# cpu_board.net
KiCad netlist of a schematic drawn in Altium Designer
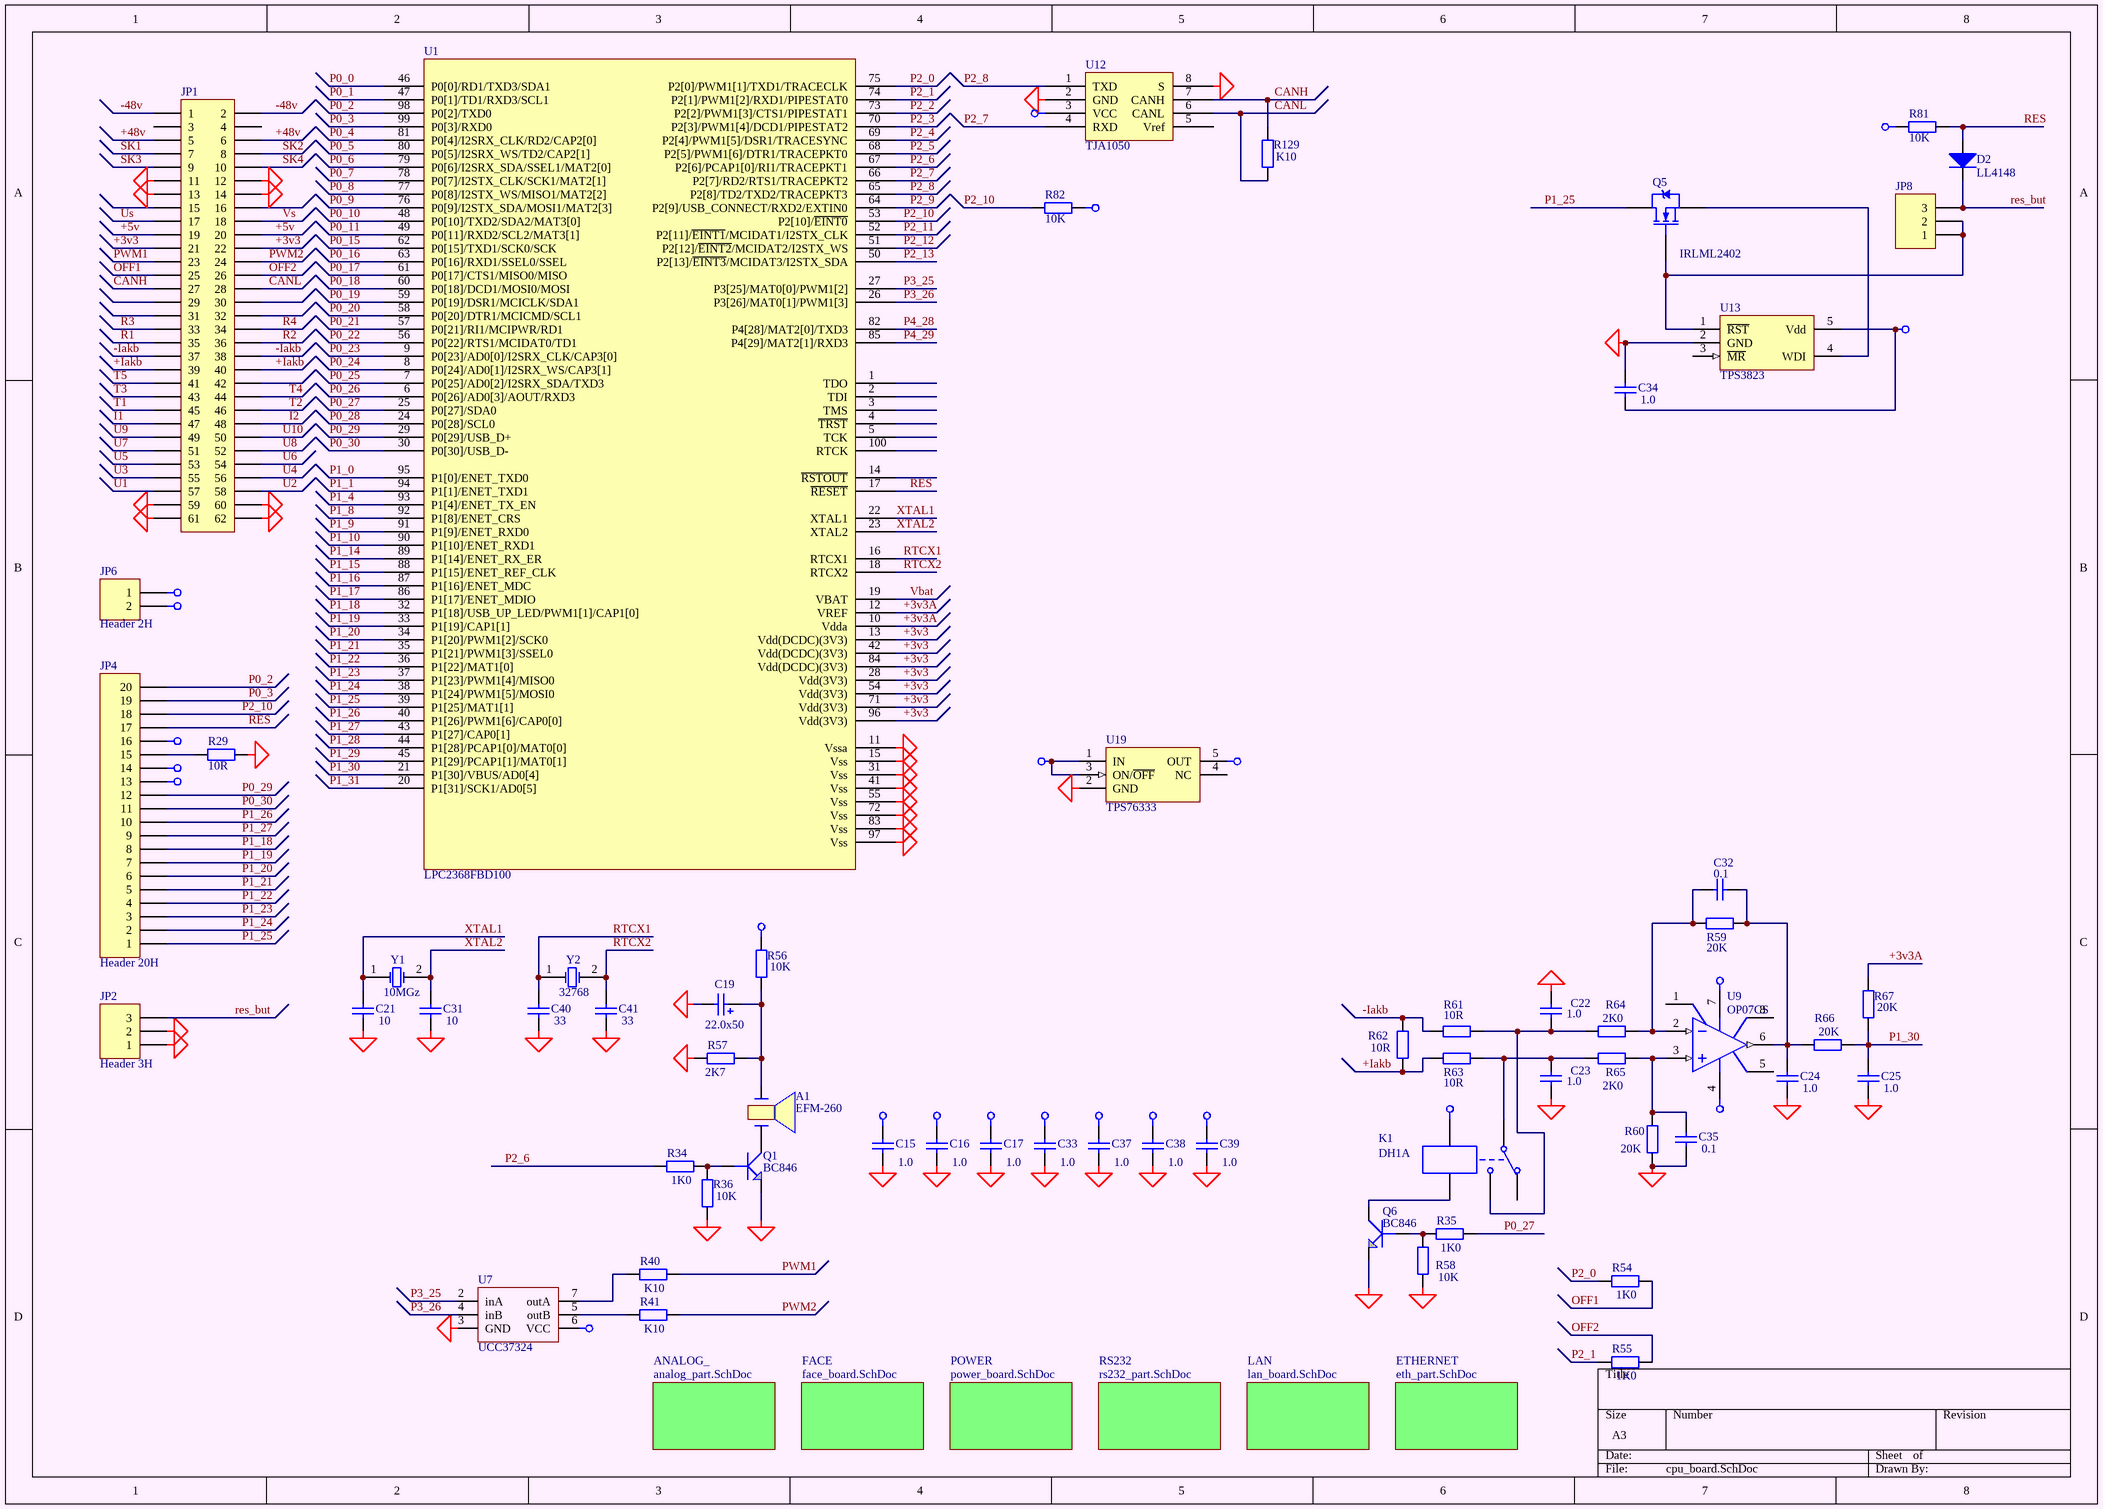
[diagram p0: cpu_board.SchDoc]

(export (version "E")
  (design (tool "Eeschema 10.0.6"))
  (components
    (comp (ref "A1") (value "EFM-260") (footprint "Pjezo15") (libsource (lib "PAL") (part "PJEZ0")))
    (comp (ref "C15")
      (value "1.0")
      (footprint "C3216-1206")
      (description "Capacitor (Semiconductor SIM Model)")
      (fields (field (name "MANUFACTURER") "Generic Components") (field (name "PUBLISHER") "Altium Limited"))
      (libsource (lib "Miscellaneous Devices") (part "Cap Semi"))
    )
    (comp (ref "C16")
      (value "1.0")
      (footprint "C3216-1206")
      (description "Capacitor (Semiconductor SIM Model)")
      (fields (field (name "MANUFACTURER") "Generic Components") (field (name "PUBLISHER") "Altium Limited"))
      (libsource (lib "Miscellaneous Devices") (part "Cap Semi"))
    )
    (comp (ref "C17")
      (value "1.0")
      (footprint "_1206")
      (description "Capacitor (Semiconductor SIM Model)")
      (fields (field (name "MANUFACTURER") "Generic Components") (field (name "PUBLISHER") "Altium Limited"))
      (libsource (lib "Miscellaneous Devices") (part "Cap Semi"))
    )
    (comp (ref "C19")
      (value "22.0x50")
      (footprint "el3")
      (description "Polarized Capacitor (Radial)")
      (fields (field (name "MANUFACTURER") "Generic Components") (field (name "PUBLISHER") "Altium Limited"))
      (libsource (lib "PAL") (part "Cap Pol1"))
    )
    (comp (ref "C21")
      (value "10")
      (footprint "_1206")
      (description "Capacitor (Semiconductor SIM Model)")
      (fields (field (name "MANUFACTURER") "Generic Components") (field (name "PUBLISHER") "Altium Limited"))
      (libsource (lib "Miscellaneous Devices") (part "Cap Semi"))
    )
    (comp (ref "C22")
      (value "1.0")
      (footprint "_1206")
      (description "Capacitor (Semiconductor SIM Model)")
      (fields (field (name "MANUFACTURER") "Generic Components") (field (name "PUBLISHER") "Altium Limited"))
      (libsource (lib "Miscellaneous Devices") (part "Cap Semi"))
    )
    (comp (ref "C23")
      (value "1.0")
      (footprint "_1206")
      (description "Capacitor (Semiconductor SIM Model)")
      (fields (field (name "MANUFACTURER") "Generic Components") (field (name "PUBLISHER") "Altium Limited"))
      (libsource (lib "Miscellaneous Devices") (part "Cap Semi"))
    )
    (comp (ref "C24")
      (value "1.0")
      (footprint "_1206")
      (description "Capacitor (Semiconductor SIM Model)")
      (fields (field (name "MANUFACTURER") "Generic Components") (field (name "PUBLISHER") "Altium Limited"))
      (libsource (lib "Miscellaneous Devices") (part "Cap Semi"))
    )
    (comp (ref "C25")
      (value "1.0")
      (footprint "_1206")
      (description "Capacitor (Semiconductor SIM Model)")
      (fields (field (name "MANUFACTURER") "Generic Components") (field (name "PUBLISHER") "Altium Limited"))
      (libsource (lib "Miscellaneous Devices") (part "Cap Semi"))
    )
    (comp (ref "C31")
      (value "10")
      (footprint "_1206")
      (description "Capacitor (Semiconductor SIM Model)")
      (fields (field (name "MANUFACTURER") "Generic Components") (field (name "PUBLISHER") "Altium Limited"))
      (libsource (lib "Miscellaneous Devices") (part "Cap Semi"))
    )
    (comp (ref "C32")
      (value "0.1")
      (footprint "_1206")
      (description "Capacitor (Semiconductor SIM Model)")
      (fields (field (name "MANUFACTURER") "Generic Components") (field (name "PUBLISHER") "Altium Limited"))
      (libsource (lib "Miscellaneous Devices") (part "Cap Semi"))
    )
    (comp (ref "C33")
      (value "1.0")
      (footprint "_1206")
      (description "Capacitor (Semiconductor SIM Model)")
      (fields (field (name "MANUFACTURER") "Generic Components") (field (name "PUBLISHER") "Altium Limited"))
      (libsource (lib "Miscellaneous Devices") (part "Cap Semi"))
    )
    (comp (ref "C34")
      (value "1.0")
      (footprint "_1206")
      (description "Capacitor")
      (fields (field (name "MANUFACTURER") "Generic Components") (field (name "PUBLISHER") "Altium Limited"))
      (libsource (lib "Miscellaneous Devices") (part "Cap Semi"))
    )
    (comp (ref "C35")
      (value "0.1")
      (footprint "_1206")
      (description "Capacitor (Semiconductor SIM Model)")
      (fields (field (name "MANUFACTURER") "Generic Components") (field (name "PUBLISHER") "Altium Limited"))
      (libsource (lib "Miscellaneous Devices") (part "Cap Semi"))
    )
    (comp (ref "C37")
      (value "1.0")
      (footprint "_1206")
      (description "Capacitor (Semiconductor SIM Model)")
      (fields (field (name "MANUFACTURER") "Generic Components") (field (name "PUBLISHER") "Altium Limited"))
      (libsource (lib "Miscellaneous Devices") (part "Cap Semi"))
    )
    (comp (ref "C38")
      (value "1.0")
      (footprint "_1206")
      (description "Capacitor (Semiconductor SIM Model)")
      (fields (field (name "MANUFACTURER") "Generic Components") (field (name "PUBLISHER") "Altium Limited"))
      (libsource (lib "Miscellaneous Devices") (part "Cap Semi"))
    )
    (comp (ref "C39")
      (value "1.0")
      (footprint "_1206")
      (description "Capacitor (Semiconductor SIM Model)")
      (fields (field (name "MANUFACTURER") "Generic Components") (field (name "PUBLISHER") "Altium Limited"))
      (libsource (lib "Miscellaneous Devices") (part "Cap Semi"))
    )
    (comp (ref "C40")
      (value "33")
      (footprint "_1206")
      (description "Capacitor (Semiconductor SIM Model)")
      (fields (field (name "MANUFACTURER") "Generic Components") (field (name "PUBLISHER") "Altium Limited"))
      (libsource (lib "Miscellaneous Devices") (part "Cap Semi"))
    )
    (comp (ref "C41")
      (value "33")
      (footprint "_1206")
      (description "Capacitor (Semiconductor SIM Model)")
      (fields (field (name "MANUFACTURER") "Generic Components") (field (name "PUBLISHER") "Altium Limited"))
      (libsource (lib "Miscellaneous Devices") (part "Cap Semi"))
    )
    (comp (ref "D2")
      (value "LL4148")
      (footprint "_1206d")
      (description "Default Diode")
      (fields (field (name "MANUFACTURER") "Generic Components") (field (name "PUBLISHER") "Altium Limited"))
      (libsource (lib "PAL") (part "Diode"))
    )
    (comp (ref "JP1")
      (value "~")
      (footprint "HDR2X30")
      (description "Header, 30-Pin, Dual row")
      (fields (field (name "MANUFACTURER") "Generic Components") (field (name "PUBLISHER") "Altium Limited"))
      (libsource (lib "UKU205") (part "Header 31X2"))
    )
    (comp (ref "JP2")
      (value "Header 3H")
      (footprint "HDR1X3H")
      (description "Header, 3-Pin,  Right Angle")
      (fields (field (name "MANUFACTURER") "Generic Components") (field (name "PUBLISHER") "Altium Limited"))
      (libsource (lib "Miscellaneous Connectors") (part "Header 3H"))
    )
    (comp (ref "JP4")
      (value "Header 20H")
      (footprint "HDR1X20H")
      (description "Header, 20-Pin,  Right Angle")
      (fields (field (name "MANUFACTURER") "Generic Components") (field (name "PUBLISHER") "Altium Limited"))
      (libsource (lib "Miscellaneous Connectors") (part "Header 20H"))
    )
    (comp (ref "JP6")
      (value "Header 2H")
      (footprint "HDR1X2H")
      (description "Header, 2-Pin,  Right Angle")
      (fields (field (name "MANUFACTURER") "Generic Components") (field (name "PUBLISHER") "Altium Limited"))
      (libsource (lib "Miscellaneous Connectors") (part "Header 2H"))
    )
    (comp (ref "JP8")
      (value "PLS-3")
      (footprint "HDR1X3")
      (description "Header, 3-Pin")
      (fields (field (name "MANUFACTURER") "Generic Components") (field (name "PUBLISHER") "Altium Limited"))
      (libsource (lib "Miscellaneous Connectors") (part "Header 3"))
    )
    (comp (ref "K1")
      (value "DH1A")
      (footprint "kuan")
      (description "Single-Pole Dual-Throw Relay")
      (fields (field (name "MANUFACTURER") "Generic Components") (field (name "PUBLISHER") "Altium Limited"))
      (libsource (lib "PAL") (part "BS115"))
    )
    (comp (ref "Q1") (value "BC846") (footprint "SO-G3") (libsource (lib "MAIN") (part "GT122")))
    (comp (ref "Q5")
      (value "IRLML2402")
      (footprint "SO-G3")
      (description "HEXFET Power MOSFET")
      (fields
        (field (name "MANUFACTURER") "International Rectifier")
        (field (name "ALTIUM_VALUE") "IRLML2402")
        (field (name "PUBLISHER") "Altium Limited")
      )
      (libsource (lib "IR Discrete MOSFET") (part "IRLML2402"))
    )
    (comp (ref "Q6") (value "BC846") (footprint "SO-G3") (libsource (lib "MAIN") (part "GT122")))
    (comp (ref "R29")
      (value "10R")
      (footprint "_1206")
      (description "Resistor")
      (fields (field (name "MANUFACTURER") "Generic Components") (field (name "PUBLISHER") "Altium Limited"))
      (libsource (lib "") (part "Res2_1"))
    )
    (comp (ref "R34")
      (value "1K0")
      (footprint "_1206")
      (description "Resistor")
      (fields (field (name "MANUFACTURER") "Generic Components") (field (name "PUBLISHER") "Altium Limited"))
      (libsource (lib "") (part "Res2_2"))
    )
    (comp (ref "R35")
      (value "1K0")
      (footprint "_1206")
      (description "Resistor")
      (fields (field (name "MANUFACTURER") "Generic Components") (field (name "PUBLISHER") "Altium Limited"))
      (libsource (lib "") (part "Res2_3"))
    )
    (comp (ref "R36")
      (value "10K")
      (footprint "_1206")
      (description "Resistor")
      (fields (field (name "MANUFACTURER") "Generic Components") (field (name "PUBLISHER") "Altium Limited"))
      (libsource (lib "Miscellaneous Devices") (part "Res2"))
    )
    (comp (ref "R40")
      (value "K10")
      (footprint "_1206")
      (description "Resistor")
      (fields (field (name "MANUFACTURER") "Generic Components") (field (name "PUBLISHER") "Altium Limited"))
      (libsource (lib "") (part "Res2_1"))
    )
    (comp (ref "R41")
      (value "K10")
      (footprint "_1206")
      (description "Resistor")
      (fields (field (name "MANUFACTURER") "Generic Components") (field (name "PUBLISHER") "Altium Limited"))
      (libsource (lib "") (part "Res2_1"))
    )
    (comp (ref "R54")
      (value "1K0")
      (footprint "_1206")
      (description "Resistor")
      (fields (field (name "MANUFACTURER") "Generic Components") (field (name "PUBLISHER") "Altium Limited"))
      (libsource (lib "") (part "Res2_2"))
    )
    (comp (ref "R55")
      (value "1K0")
      (footprint "_1206")
      (description "Resistor")
      (fields (field (name "MANUFACTURER") "Generic Components") (field (name "PUBLISHER") "Altium Limited"))
      (libsource (lib "") (part "Res2_2"))
    )
    (comp (ref "R56")
      (value "10K")
      (footprint "_1206")
      (description "Resistor")
      (fields (field (name "MANUFACTURER") "Generic Components") (field (name "PUBLISHER") "Altium Limited"))
      (libsource (lib "Miscellaneous Devices") (part "Res2"))
    )
    (comp (ref "R57")
      (value "2K7")
      (footprint "_1206")
      (description "Resistor")
      (fields (field (name "MANUFACTURER") "Generic Components") (field (name "PUBLISHER") "Altium Limited"))
      (libsource (lib "") (part "Res2_2"))
    )
    (comp (ref "R58")
      (value "10K")
      (footprint "_1206")
      (description "Resistor")
      (fields (field (name "MANUFACTURER") "Generic Components") (field (name "PUBLISHER") "Altium Limited"))
      (libsource (lib "") (part "Res2_2"))
    )
    (comp (ref "R59")
      (value "20K")
      (footprint "_1206")
      (description "Resistor")
      (fields (field (name "MANUFACTURER") "Generic Components") (field (name "PUBLISHER") "Altium Limited"))
      (libsource (lib "") (part "Res2_1"))
    )
    (comp (ref "R60")
      (value "20K")
      (footprint "_1206")
      (description "Resistor")
      (fields (field (name "MANUFACTURER") "Generic Components") (field (name "PUBLISHER") "Altium Limited"))
      (libsource (lib "Miscellaneous Devices") (part "Res2"))
    )
    (comp (ref "R61")
      (value "10R")
      (footprint "_1206")
      (description "Resistor")
      (fields (field (name "MANUFACTURER") "Generic Components") (field (name "PUBLISHER") "Altium Limited"))
      (libsource (lib "") (part "Res2_1"))
    )
    (comp (ref "R62")
      (value "10R")
      (footprint "_1206")
      (description "Resistor")
      (fields (field (name "MANUFACTURER") "Generic Components") (field (name "PUBLISHER") "Altium Limited"))
      (libsource (lib "Miscellaneous Devices") (part "Res2"))
    )
    (comp (ref "R63")
      (value "10R")
      (footprint "_1206")
      (description "Resistor")
      (fields (field (name "MANUFACTURER") "Generic Components") (field (name "PUBLISHER") "Altium Limited"))
      (libsource (lib "") (part "Res2_1"))
    )
    (comp (ref "R64")
      (value "2K0")
      (footprint "_1206")
      (description "Resistor")
      (fields (field (name "MANUFACTURER") "Generic Components") (field (name "PUBLISHER") "Altium Limited"))
      (libsource (lib "") (part "Res2_2"))
    )
    (comp (ref "R65")
      (value "2K0")
      (footprint "_1206")
      (description "Resistor")
      (fields (field (name "MANUFACTURER") "Generic Components") (field (name "PUBLISHER") "Altium Limited"))
      (libsource (lib "") (part "Res2_2"))
    )
    (comp (ref "R66")
      (value "20K")
      (footprint "_1206")
      (description "Resistor")
      (fields (field (name "MANUFACTURER") "Generic Components") (field (name "PUBLISHER") "Altium Limited"))
      (libsource (lib "") (part "Res2_2"))
    )
    (comp (ref "R67")
      (value "20K")
      (footprint "_1206")
      (description "Resistor")
      (fields (field (name "MANUFACTURER") "Generic Components") (field (name "PUBLISHER") "Altium Limited"))
      (libsource (lib "") (part "Res2_2"))
    )
    (comp (ref "R81")
      (value "10K")
      (footprint "_1206")
      (description "Resistor")
      (fields (field (name "MANUFACTURER") "Generic Components") (field (name "PUBLISHER") "Altium Limited"))
      (libsource (lib "") (part "Res2_1"))
    )
    (comp (ref "R82")
      (value "10K")
      (footprint "_1206")
      (description "Resistor")
      (fields (field (name "MANUFACTURER") "Generic Components") (field (name "PUBLISHER") "Altium Limited"))
      (libsource (lib "") (part "Res2_1"))
    )
    (comp (ref "R129")
      (value "K10")
      (footprint "_1206")
      (description "Resistor")
      (fields (field (name "MANUFACTURER") "Generic Components") (field (name "PUBLISHER") "Altium Limited"))
      (libsource (lib "Miscellaneous Devices") (part "Res2"))
    )
    (comp (ref "U1")
      (value "LPC2368FBD100")
      (footprint "LPC2368")
      (libsource (lib "PAL") (part "LPC2368FBD100"))
    )
    (comp (ref "U7") (value "UCC37324") (footprint "SO-G8") (libsource (lib "PAL") (part "UCC37324")))
    (comp (ref "U9")
      (value "OP07CS")
      (footprint "SO-G8")
      (description "Ultra-Low Offset Voltage Operational Amplifier")
      (fields (field (name "MANUFACTURER") "Analog Devices") (field (name "PUBLISHER") "Altium Limited"))
      (libsource (lib "AD Operational Amplifier") (part "OP07CS"))
    )
    (comp (ref "U12") (value "TJA1050") (footprint "SO-G8") (libsource (lib "PAL") (part "TJA1050")))
    (comp (ref "U13")
      (value "TPS3823")
      (footprint "SO-G5/P.95")
      (description "Reset IC")
      (fields
        (field (name "MANUFACTURER") "National Semiconductor")
        (field (name "PUBLISHER") "Altium Limited")
      )
      (libsource (lib "PAL") (part "TPS3823"))
    )
    (comp (ref "U19")
      (value "TPS76333")
      (footprint "SO-G5/P.95")
      (description "Micropower SOT, 50 mA Ultra Low-Dropout Regulator")
      (fields
        (field (name "MANUFACTURER") "National Semiconductor")
        (field (name "PUBLISHER") "Altium Limited")
      )
      (libsource (lib "NSC Power Mgt Voltage Regulator") (part "LP2980AIM5-3.3"))
    )
    (comp (ref "Y1")
      (value "10MGz")
      (footprint "QWARZ1")
      (description "Crystal Oscillator")
      (fields (field (name "MANUFACTURER") "Generic Components") (field (name "PUBLISHER") "Altium Limited"))
      (libsource (lib "") (part "XTAL_1"))
    )
    (comp (ref "Y2")
      (value "32768")
      (footprint "QWARZ2")
      (description "Crystal Oscillator")
      (fields (field (name "MANUFACTURER") "Generic Components") (field (name "PUBLISHER") "Altium Limited"))
      (libsource (lib "Miscellaneous Devices") (part "XTAL"))
    )
  )
  (nets
    (net (code "1") (name "+3v3") (class "Default")
      (node (ref "C34") (pin "1") (pinfunction "1_1") (pintype "passive"))
      (node (ref "C37") (pin "2") (pinfunction "2_2") (pintype "passive"))
      (node (ref "C38") (pin "2") (pinfunction "2_2") (pintype "passive"))
      (node (ref "C39") (pin "2") (pinfunction "2_2") (pintype "passive"))
      (node (ref "JP1") (pin "21") (pinfunction "21_21") (pintype "passive"))
      (node (ref "JP1") (pin "22") (pinfunction "22_22") (pintype "passive"))
      (node (ref "JP4") (pin "16") (pinfunction "16_16") (pintype "passive"))
      (node (ref "R81") (pin "2") (pinfunction "2_2") (pintype "passive"))
      (node (ref "R82") (pin "1") (pinfunction "1_1") (pintype "passive"))
      (node (ref "U1") (pin "13") (pinfunction "Vdd(DCDC)(3V3)_13") (pintype "passive"))
      (node (ref "U1") (pin "28") (pinfunction "Vdd(3V3)_28") (pintype "passive"))
      (node (ref "U1") (pin "42") (pinfunction "Vdd(DCDC)(3V3)_42") (pintype "passive"))
      (node (ref "U1") (pin "54") (pinfunction "Vdd(3V3)_54") (pintype "passive"))
      (node (ref "U1") (pin "71") (pinfunction "Vdd(3V3)_71") (pintype "passive"))
      (node (ref "U1") (pin "84") (pinfunction "Vdd(DCDC)(3V3)_84") (pintype "passive"))
      (node (ref "U1") (pin "96") (pinfunction "Vdd(3V3)_96") (pintype "passive"))
      (node (ref "U13") (pin "5") (pinfunction "Vdd_5") (pintype "power_in"))
    )
    (net (code "2") (name "+3v3A") (class "Default")
      (node (ref "C17") (pin "2") (pinfunction "2_2") (pintype "passive"))
      (node (ref "C33") (pin "2") (pinfunction "2_2") (pintype "passive"))
      (node (ref "R67") (pin "2") (pinfunction "2_2") (pintype "passive"))
      (node (ref "U1") (pin "10") (pinfunction "Vdda_10") (pintype "passive"))
      (node (ref "U1") (pin "12") (pinfunction "VREF_12") (pintype "passive"))
      (node (ref "U19") (pin "5") (pinfunction "OUT_5") (pintype "power_in"))
    )
    (net (code "3") (name "+5v") (class "Default")
      (node (ref "C15") (pin "2") (pinfunction "2_2") (pintype "passive"))
      (node (ref "JP1") (pin "19") (pinfunction "19_19") (pintype "passive"))
      (node (ref "JP1") (pin "20") (pinfunction "20_20") (pintype "passive"))
      (node (ref "JP4") (pin "13") (pinfunction "13_13") (pintype "passive"))
      (node (ref "JP4") (pin "14") (pinfunction "14_14") (pintype "passive"))
      (node (ref "K1") (pin "4") (pinfunction "4_4") (pintype "passive"))
      (node (ref "U12") (pin "3") (pinfunction "VCC_3") (pintype "passive"))
      (node (ref "U19") (pin "1") (pinfunction "IN_1") (pintype "power_in"))
      (node (ref "U19") (pin "3") (pinfunction "ON/~{OFF}_3") (pintype "input"))
      (node (ref "U7") (pin "6") (pinfunction "VCC_6") (pintype "passive"))
      (node (ref "U9") (pin "7") (pinfunction "V+_7") (pintype "power_in"))
    )
    (net (code "4") (name "+5viz") (class "Default")
      (node (ref "JP6") (pin "1") (pinfunction "1_1") (pintype "passive"))
    )
    (net (code "5") (name "+48v") (class "Default")
      (node (ref "JP1") (pin "5") (pinfunction "5_5") (pintype "passive"))
      (node (ref "JP1") (pin "6") (pinfunction "6_6") (pintype "passive"))
      (node (ref "R56") (pin "2") (pinfunction "2_2") (pintype "passive"))
    )
    (net (code "6") (name "-5v") (class "Default")
      (node (ref "C16") (pin "2") (pinfunction "2_2") (pintype "passive"))
      (node (ref "U9") (pin "4") (pinfunction "V-_4") (pintype "power_in"))
    )
    (net (code "7") (name "-5viz") (class "Default")
      (node (ref "JP6") (pin "2") (pinfunction "2_2") (pintype "passive"))
    )
    (net (code "8") (name "/+Iakb") (class "Default")
      (node (ref "JP1") (pin "39") (pinfunction "39_39") (pintype "passive"))
      (node (ref "JP1") (pin "40") (pinfunction "40_40") (pintype "passive"))
      (node (ref "R62") (pin "1") (pinfunction "1_1") (pintype "passive"))
      (node (ref "R63") (pin "2") (pinfunction "2_2") (pintype "passive"))
    )
    (net (code "9") (name "/-48v") (class "Default")
      (node (ref "JP1") (pin "1") (pinfunction "1_1") (pintype "passive"))
      (node (ref "JP1") (pin "2") (pinfunction "2_2") (pintype "passive"))
    )
    (net (code "10") (name "/-Iakb") (class "Default")
      (node (ref "JP1") (pin "37") (pinfunction "37_37") (pintype "passive"))
      (node (ref "JP1") (pin "38") (pinfunction "38_38") (pintype "passive"))
      (node (ref "R61") (pin "2") (pinfunction "2_2") (pintype "passive"))
      (node (ref "R62") (pin "2") (pinfunction "2_2") (pintype "passive"))
    )
    (net (code "12") (name "/CANH") (class "Default")
      (node (ref "JP1") (pin "27") (pinfunction "27_27") (pintype "passive"))
      (node (ref "R129") (pin "2") (pinfunction "2_2") (pintype "passive"))
      (node (ref "U12") (pin "7") (pinfunction "CANH_7") (pintype "passive"))
    )
    (net (code "13") (name "/CANL") (class "Default")
      (node (ref "JP1") (pin "28") (pinfunction "28_28") (pintype "passive"))
      (node (ref "R129") (pin "1") (pinfunction "1_1") (pintype "passive"))
      (node (ref "U12") (pin "6") (pinfunction "CANL_6") (pintype "passive"))
    )
    (net (code "14") (name "/I1") (class "Default")
      (node (ref "JP1") (pin "47") (pinfunction "47_47") (pintype "passive"))
    )
    (net (code "15") (name "/I2") (class "Default")
      (node (ref "JP1") (pin "48") (pinfunction "48_48") (pintype "passive"))
    )
    (net (code "16") (name "/OFF1") (class "Default")
      (node (ref "JP1") (pin "25") (pinfunction "25_25") (pintype "passive"))
      (node (ref "R54") (pin "2") (pinfunction "2_2") (pintype "passive"))
    )
    (net (code "17") (name "/OFF2") (class "Default")
      (node (ref "JP1") (pin "26") (pinfunction "26_26") (pintype "passive"))
      (node (ref "R55") (pin "2") (pinfunction "2_2") (pintype "passive"))
    )
    (net (code "18") (name "/P0_0") (class "Default")
      (node (ref "U1") (pin "46") (pinfunction "P0[0]/RD1/TXD3/SDA1_46") (pintype "passive"))
    )
    (net (code "19") (name "/P0_1") (class "Default")
      (node (ref "U1") (pin "47") (pinfunction "P0[1]/TD1/RXD3/SCL1_47") (pintype "passive"))
    )
    (net (code "20") (name "/P0_2") (class "Default")
      (node (ref "JP4") (pin "20") (pinfunction "20_20") (pintype "passive"))
      (node (ref "U1") (pin "98") (pinfunction "P0[2]/TXD0_98") (pintype "passive"))
    )
    (net (code "21") (name "/P0_3") (class "Default")
      (node (ref "JP4") (pin "19") (pinfunction "19_19") (pintype "passive"))
      (node (ref "U1") (pin "99") (pinfunction "P0[3]/RXD0_99") (pintype "passive"))
    )
    (net (code "22") (name "/P0_4") (class "Default")
      (node (ref "U1") (pin "81") (pinfunction "P0[4]/I2SRX_CLK/RD2/CAP2[0]_81") (pintype "passive"))
    )
    (net (code "23") (name "/P0_5") (class "Default")
      (node (ref "U1") (pin "80") (pinfunction "P0[5]/I2SRX_WS/TD2/CAP2[1]_80") (pintype "passive"))
    )
    (net (code "24") (name "/P0_6") (class "Default")
      (node (ref "U1") (pin "79") (pinfunction "P0[6]/I2SRX_SDA/SSEL1/MAT2[0]_79") (pintype "passive"))
    )
    (net (code "25") (name "/P0_7") (class "Default")
      (node (ref "U1") (pin "78") (pinfunction "P0[7]/I2STX_CLK/SCK1/MAT2[1]_78") (pintype "passive"))
    )
    (net (code "26") (name "/P0_8") (class "Default")
      (node (ref "U1") (pin "77") (pinfunction "P0[8]/I2STX_WS/MISO1/MAT2[2]_77") (pintype "passive"))
    )
    (net (code "27") (name "/P0_9") (class "Default")
      (node (ref "U1") (pin "76") (pinfunction "P0[9]/I2STX_SDA/MOSI1/MAT2[3]_76") (pintype "passive"))
    )
    (net (code "28") (name "/P0_10") (class "Default")
      (node (ref "U1") (pin "48") (pinfunction "P0[10]/TXD2/SDA2/MAT3[0]_48") (pintype "passive"))
    )
    (net (code "29") (name "/P0_11") (class "Default")
      (node (ref "U1") (pin "49") (pinfunction "P0[11]/RXD2/SCL2/MAT3[1]_49") (pintype "passive"))
    )
    (net (code "30") (name "/P0_15") (class "Default")
      (node (ref "U1") (pin "62") (pinfunction "P0[15]/TXD1/SCK0/SCK_62") (pintype "passive"))
    )
    (net (code "31") (name "/P0_16") (class "Default")
      (node (ref "U1") (pin "63") (pinfunction "P0[16]/RXD1/SSEL0/SSEL_63") (pintype "passive"))
    )
    (net (code "32") (name "/P0_17") (class "Default")
      (node (ref "U1") (pin "61") (pinfunction "P0[17]/CTS1/MISO0/MISO_61") (pintype "passive"))
    )
    (net (code "33") (name "/P0_18") (class "Default")
      (node (ref "U1") (pin "60") (pinfunction "P0[18]/DCD1/MOSI0/MOSI_60") (pintype "passive"))
    )
    (net (code "34") (name "/P0_19") (class "Default")
      (node (ref "U1") (pin "59") (pinfunction "P0[19]/DSR1/MCICLK/SDA1_59") (pintype "passive"))
    )
    (net (code "35") (name "/P0_20") (class "Default")
      (node (ref "U1") (pin "58") (pinfunction "P0[20]/DTR1/MCICMD/SCL1_58") (pintype "passive"))
    )
    (net (code "36") (name "/P0_21") (class "Default")
      (node (ref "U1") (pin "57") (pinfunction "P0[21]/RI1/MCIPWR/RD1_57") (pintype "passive"))
    )
    (net (code "37") (name "/P0_22") (class "Default")
      (node (ref "U1") (pin "56") (pinfunction "P0[22]/RTS1/MCIDAT0/TD1_56") (pintype "passive"))
    )
    (net (code "38") (name "/P0_23") (class "Default")
      (node (ref "U1") (pin "9") (pinfunction "P0[23]/AD0[0]/I2SRX_CLK/CAP3[0]_9") (pintype "passive"))
    )
    (net (code "39") (name "/P0_24") (class "Default")
      (node (ref "U1") (pin "8") (pinfunction "P0[24]/AD0[1]/I2SRX_WS/CAP3[1]_8") (pintype "passive"))
    )
    (net (code "40") (name "/P0_25") (class "Default")
      (node (ref "U1") (pin "7") (pinfunction "P0[25]/AD0[2]/I2SRX_SDA/TXD3_7") (pintype "passive"))
    )
    (net (code "41") (name "/P0_26") (class "Default")
      (node (ref "U1") (pin "6") (pinfunction "P0[26]/AD0[3]/AOUT/RXD3_6") (pintype "passive"))
    )
    (net (code "42") (name "/P0_27") (class "Default")
      (node (ref "R35") (pin "1") (pinfunction "1_1") (pintype "passive"))
      (node (ref "U1") (pin "25") (pinfunction "P0[27]/SDA0_25") (pintype "passive"))
    )
    (net (code "43") (name "/P0_28") (class "Default")
      (node (ref "U1") (pin "24") (pinfunction "P0[28]/SCL0_24") (pintype "passive"))
    )
    (net (code "44") (name "/P0_29") (class "Default")
      (node (ref "JP4") (pin "12") (pinfunction "12_12") (pintype "passive"))
      (node (ref "U1") (pin "29") (pinfunction "P0[29]/USB_D+_29") (pintype "passive"))
    )
    (net (code "45") (name "/P0_30") (class "Default")
      (node (ref "JP4") (pin "11") (pinfunction "11_11") (pintype "passive"))
      (node (ref "U1") (pin "30") (pinfunction "P0[30]/USB_D-_30") (pintype "passive"))
    )
    (net (code "46") (name "/P1_0") (class "Default")
      (node (ref "U1") (pin "95") (pinfunction "P1[0]/ENET_TXD0_95") (pintype "passive"))
    )
    (net (code "47") (name "/P1_1") (class "Default")
      (node (ref "U1") (pin "94") (pinfunction "P1[1]/ENET_TXD1_94") (pintype "passive"))
    )
    (net (code "48") (name "/P1_4") (class "Default")
      (node (ref "U1") (pin "93") (pinfunction "P1[4]/ENET_TX_EN_93") (pintype "passive"))
    )
    (net (code "49") (name "/P1_8") (class "Default")
      (node (ref "U1") (pin "92") (pinfunction "P1[8]/ENET_CRS_92") (pintype "passive"))
    )
    (net (code "50") (name "/P1_9") (class "Default")
      (node (ref "U1") (pin "91") (pinfunction "P1[9]/ENET_RXD0_91") (pintype "passive"))
    )
    (net (code "51") (name "/P1_10") (class "Default")
      (node (ref "U1") (pin "90") (pinfunction "P1[10]/ENET_RXD1_90") (pintype "passive"))
    )
    (net (code "52") (name "/P1_14") (class "Default")
      (node (ref "U1") (pin "89") (pinfunction "P1[14]/ENET_RX_ER_89") (pintype "passive"))
    )
    (net (code "53") (name "/P1_15") (class "Default")
      (node (ref "U1") (pin "88") (pinfunction "P1[15]/ENET_REF_CLK_88") (pintype "passive"))
    )
    (net (code "54") (name "/P1_16") (class "Default")
      (node (ref "U1") (pin "87") (pinfunction "P1[16]/ENET_MDC_87") (pintype "passive"))
    )
    (net (code "55") (name "/P1_17") (class "Default")
      (node (ref "U1") (pin "86") (pinfunction "P1[17]/ENET_MDIO_86") (pintype "passive"))
    )
    (net (code "56") (name "/P1_18") (class "Default")
      (node (ref "JP4") (pin "8") (pinfunction "8_8") (pintype "passive"))
      (node (ref "U1") (pin "32") (pinfunction "P1[18]/USB_UP_LED/PWM1[1]/CAP1[0]_32") (pintype "passive"))
    )
    (net (code "57") (name "/P1_19") (class "Default")
      (node (ref "JP4") (pin "7") (pinfunction "7_7") (pintype "passive"))
      (node (ref "U1") (pin "33") (pinfunction "P1[19]/CAP1[1]_33") (pintype "passive"))
    )
    (net (code "58") (name "/P1_20") (class "Default")
      (node (ref "JP4") (pin "6") (pinfunction "6_6") (pintype "passive"))
      (node (ref "U1") (pin "34") (pinfunction "P1[20]/PWM1[2]/SCK0_34") (pintype "passive"))
    )
    (net (code "59") (name "/P1_21") (class "Default")
      (node (ref "JP4") (pin "5") (pinfunction "5_5") (pintype "passive"))
      (node (ref "U1") (pin "35") (pinfunction "P1[21]/PWM1[3]/SSEL0_35") (pintype "passive"))
    )
    (net (code "60") (name "/P1_22") (class "Default")
      (node (ref "JP4") (pin "4") (pinfunction "4_4") (pintype "passive"))
      (node (ref "U1") (pin "36") (pinfunction "P1[22]/MAT1[0]_36") (pintype "passive"))
    )
    (net (code "61") (name "/P1_23") (class "Default")
      (node (ref "JP4") (pin "3") (pinfunction "3_3") (pintype "passive"))
      (node (ref "U1") (pin "37") (pinfunction "P1[23]/PWM1[4]/MISO0_37") (pintype "passive"))
    )
    (net (code "62") (name "/P1_24") (class "Default")
      (node (ref "JP4") (pin "2") (pinfunction "2_2") (pintype "passive"))
      (node (ref "U1") (pin "38") (pinfunction "P1[24]/PWM1[5]/MOSI0_38") (pintype "passive"))
    )
    (net (code "63") (name "/P1_25") (class "Default")
      (node (ref "JP4") (pin "1") (pinfunction "1_1") (pintype "passive"))
      (node (ref "Q5") (pin "3") (pinfunction "D_3") (pintype "passive"))
      (node (ref "U1") (pin "39") (pinfunction "P1[25]/MAT1[1]_39") (pintype "passive"))
    )
    (net (code "64") (name "/P1_26") (class "Default")
      (node (ref "JP4") (pin "10") (pinfunction "10_10") (pintype "passive"))
      (node (ref "U1") (pin "40") (pinfunction "P1[26]/PWM1[6]/CAP0[0]_40") (pintype "passive"))
    )
    (net (code "65") (name "/P1_27") (class "Default")
      (node (ref "JP4") (pin "9") (pinfunction "9_9") (pintype "passive"))
      (node (ref "U1") (pin "43") (pinfunction "P1[27]/CAP0[1]_43") (pintype "passive"))
    )
    (net (code "66") (name "/P1_28") (class "Default")
      (node (ref "U1") (pin "44") (pinfunction "P1[28]/PCAP1[0]/MAT0[0]_44") (pintype "passive"))
    )
    (net (code "67") (name "/P1_29") (class "Default")
      (node (ref "U1") (pin "45") (pinfunction "P1[29]/PCAP1[1]/MAT0[1]_45") (pintype "passive"))
    )
    (net (code "68") (name "/P1_30") (class "Default")
      (node (ref "C25") (pin "2") (pinfunction "2_2") (pintype "passive"))
      (node (ref "R66") (pin "2") (pinfunction "2_2") (pintype "passive"))
      (node (ref "R67") (pin "1") (pinfunction "1_1") (pintype "passive"))
      (node (ref "U1") (pin "21") (pinfunction "P1[30]/VBUS/AD0[4]_21") (pintype "passive"))
    )
    (net (code "69") (name "/P1_31") (class "Default")
      (node (ref "U1") (pin "20") (pinfunction "P1[31]/SCK1/AD0[5]_20") (pintype "passive"))
    )
    (net (code "70") (name "/P2_0") (class "Default")
      (node (ref "R54") (pin "1") (pinfunction "1_1") (pintype "passive"))
      (node (ref "U1") (pin "75") (pinfunction "P2[0]/PWM1[1]/TXD1/TRACECLK_75") (pintype "passive"))
    )
    (net (code "71") (name "/P2_1") (class "Default")
      (node (ref "R55") (pin "1") (pinfunction "1_1") (pintype "passive"))
      (node (ref "U1") (pin "74") (pinfunction "P2[1]/PWM1[2]/RXD1/PIPESTAT0_74") (pintype "passive"))
    )
    (net (code "72") (name "/P2_2") (class "Default")
      (node (ref "U1") (pin "73") (pinfunction "P2[2]/PWM1[3]/CTS1/PIPESTAT1_73") (pintype "passive"))
    )
    (net (code "73") (name "/P2_3") (class "Default")
      (node (ref "U1") (pin "70") (pinfunction "P2[3]/PWM1[4]/DCD1/PIPESTAT2_70") (pintype "passive"))
    )
    (net (code "74") (name "/P2_4") (class "Default")
      (node (ref "U1") (pin "69") (pinfunction "P2[4]/PWM1[5]/DSR1/TRACESYNC_69") (pintype "passive"))
    )
    (net (code "75") (name "/P2_5") (class "Default")
      (node (ref "U1") (pin "68") (pinfunction "P2[5]/PWM1[6]/DTR1/TRACEPKT0_68") (pintype "passive"))
    )
    (net (code "76") (name "/P2_6") (class "Default")
      (node (ref "R34") (pin "1") (pinfunction "1_1") (pintype "passive"))
      (node (ref "U1") (pin "67") (pinfunction "P2[6]/PCAP1[0]/RI1/TRACEPKT1_67") (pintype "passive"))
    )
    (net (code "77") (name "/P2_7") (class "Default")
      (node (ref "U1") (pin "66") (pinfunction "P2[7]/RD2/RTS1/TRACEPKT2_66") (pintype "passive"))
      (node (ref "U12") (pin "4") (pinfunction "RXD_4") (pintype "passive"))
    )
    (net (code "78") (name "/P2_8") (class "Default")
      (node (ref "U1") (pin "65") (pinfunction "P2[8]/TD2/TXD2/TRACEPKT3_65") (pintype "passive"))
      (node (ref "U12") (pin "1") (pinfunction "TXD_1") (pintype "passive"))
    )
    (net (code "79") (name "/P2_9") (class "Default")
      (node (ref "U1") (pin "64") (pinfunction "P2[9]/USB_CONNECT/RXD2/EXTIN0_64") (pintype "passive"))
    )
    (net (code "80") (name "/P2_10") (class "Default")
      (node (ref "JP4") (pin "18") (pinfunction "18_18") (pintype "passive"))
      (node (ref "R82") (pin "2") (pinfunction "2_2") (pintype "passive"))
      (node (ref "U1") (pin "53") (pinfunction "P2[10]/~{EINT0}_53") (pintype "passive"))
    )
    (net (code "81") (name "/P2_11") (class "Default")
      (node (ref "U1") (pin "52") (pinfunction "P2[11]/~{EINT1}/MCIDAT1/I2STX_CLK_52") (pintype "passive"))
    )
    (net (code "82") (name "/P2_12") (class "Default")
      (node (ref "U1") (pin "51") (pinfunction "P2[12]/~{EINT2}/MCIDAT2/I2STX_WS_51") (pintype "passive"))
    )
    (net (code "83") (name "/P2_13") (class "Default")
      (node (ref "U1") (pin "50") (pinfunction "P2[13]/~{EINT3}/MCIDAT3/I2STX_SDA_50") (pintype "passive"))
    )
    (net (code "84") (name "/P3_25") (class "Default")
      (node (ref "U1") (pin "27") (pinfunction "P3[25]/MAT0[0]/PWM1[2]_27") (pintype "passive"))
      (node (ref "U7") (pin "2") (pinfunction "inA_2") (pintype "passive"))
    )
    (net (code "85") (name "/P3_26") (class "Default")
      (node (ref "U1") (pin "26") (pinfunction "P3[26]/MAT0[1]/PWM1[3]_26") (pintype "passive"))
      (node (ref "U7") (pin "4") (pinfunction "inB_4") (pintype "passive"))
    )
    (net (code "86") (name "/P4_28") (class "Default")
      (node (ref "U1") (pin "82") (pinfunction "P4[28]/MAT2[0]/TXD3_82") (pintype "passive"))
    )
    (net (code "87") (name "/P4_29") (class "Default")
      (node (ref "U1") (pin "85") (pinfunction "P4[29]/MAT2[1]/RXD3_85") (pintype "passive"))
    )
    (net (code "88") (name "/PWM1") (class "Default")
      (node (ref "JP1") (pin "23") (pinfunction "23_23") (pintype "passive"))
      (node (ref "R40") (pin "1") (pinfunction "1_1") (pintype "passive"))
    )
    (net (code "89") (name "/PWM2") (class "Default")
      (node (ref "JP1") (pin "24") (pinfunction "24_24") (pintype "passive"))
      (node (ref "R41") (pin "1") (pinfunction "1_1") (pintype "passive"))
    )
    (net (code "90") (name "/R1") (class "Default")
      (node (ref "JP1") (pin "35") (pinfunction "35_35") (pintype "passive"))
    )
    (net (code "91") (name "/R2") (class "Default")
      (node (ref "JP1") (pin "36") (pinfunction "36_36") (pintype "passive"))
    )
    (net (code "92") (name "/R3") (class "Default")
      (node (ref "JP1") (pin "33") (pinfunction "33_33") (pintype "passive"))
    )
    (net (code "93") (name "/R4") (class "Default")
      (node (ref "JP1") (pin "34") (pinfunction "34_34") (pintype "passive"))
    )
    (net (code "94") (name "/RES") (class "Default")
      (node (ref "D2") (pin "1") (pinfunction "A_1") (pintype "passive"))
      (node (ref "JP4") (pin "17") (pinfunction "17_17") (pintype "passive"))
      (node (ref "R81") (pin "1") (pinfunction "1_1") (pintype "passive"))
      (node (ref "U1") (pin "17") (pinfunction "~{RESET}_17") (pintype "passive"))
    )
    (net (code "95") (name "/RTCX1") (class "Default")
      (node (ref "C40") (pin "2") (pinfunction "2_2") (pintype "passive"))
      (node (ref "U1") (pin "16") (pinfunction "RTCX1_16") (pintype "passive"))
      (node (ref "Y2") (pin "1") (pinfunction "OSC1_1") (pintype "passive"))
    )
    (net (code "96") (name "/RTCX2") (class "Default")
      (node (ref "C41") (pin "2") (pinfunction "2_2") (pintype "passive"))
      (node (ref "U1") (pin "18") (pinfunction "RTCX2_18") (pintype "passive"))
      (node (ref "Y2") (pin "2") (pinfunction "OSC2_2") (pintype "passive"))
    )
    (net (code "97") (name "/SK1") (class "Default")
      (node (ref "JP1") (pin "7") (pinfunction "7_7") (pintype "passive"))
    )
    (net (code "98") (name "/SK2") (class "Default")
      (node (ref "JP1") (pin "8") (pinfunction "8_8") (pintype "passive"))
    )
    (net (code "99") (name "/SK3") (class "Default")
      (node (ref "JP1") (pin "9") (pinfunction "9_9") (pintype "passive"))
    )
    (net (code "100") (name "/SK4") (class "Default")
      (node (ref "JP1") (pin "10") (pinfunction "10_10") (pintype "passive"))
    )
    (net (code "101") (name "/T1") (class "Default")
      (node (ref "JP1") (pin "45") (pinfunction "45_45") (pintype "passive"))
    )
    (net (code "102") (name "/T2") (class "Default")
      (node (ref "JP1") (pin "46") (pinfunction "46_46") (pintype "passive"))
    )
    (net (code "103") (name "/T3") (class "Default")
      (node (ref "JP1") (pin "43") (pinfunction "43_43") (pintype "passive"))
    )
    (net (code "104") (name "/T4") (class "Default")
      (node (ref "JP1") (pin "44") (pinfunction "44_44") (pintype "passive"))
    )
    (net (code "105") (name "/T5") (class "Default")
      (node (ref "JP1") (pin "41") (pinfunction "41_41") (pintype "passive"))
    )
    (net (code "106") (name "/U1") (class "Default")
      (node (ref "JP1") (pin "57") (pinfunction "57_57") (pintype "passive"))
    )
    (net (code "107") (name "/U2") (class "Default")
      (node (ref "JP1") (pin "58") (pinfunction "58_58") (pintype "passive"))
    )
    (net (code "108") (name "/U3") (class "Default")
      (node (ref "JP1") (pin "55") (pinfunction "55_55") (pintype "passive"))
    )
    (net (code "109") (name "/U4") (class "Default")
      (node (ref "JP1") (pin "56") (pinfunction "56_56") (pintype "passive"))
    )
    (net (code "110") (name "/U5") (class "Default")
      (node (ref "JP1") (pin "53") (pinfunction "53_53") (pintype "passive"))
    )
    (net (code "111") (name "/U6") (class "Default")
      (node (ref "JP1") (pin "54") (pinfunction "54_54") (pintype "passive"))
    )
    (net (code "112") (name "/U7") (class "Default")
      (node (ref "JP1") (pin "51") (pinfunction "51_51") (pintype "passive"))
    )
    (net (code "113") (name "/U8") (class "Default")
      (node (ref "JP1") (pin "52") (pinfunction "52_52") (pintype "passive"))
    )
    (net (code "114") (name "/U9") (class "Default")
      (node (ref "JP1") (pin "49") (pinfunction "49_49") (pintype "passive"))
    )
    (net (code "115") (name "/U10") (class "Default")
      (node (ref "JP1") (pin "50") (pinfunction "50_50") (pintype "passive"))
    )
    (net (code "116") (name "/Us") (class "Default")
      (node (ref "JP1") (pin "17") (pinfunction "17_17") (pintype "passive"))
    )
    (net (code "117") (name "/Vbat") (class "Default")
      (node (ref "U1") (pin "19") (pinfunction "VBAT_19") (pintype "passive"))
    )
    (net (code "118") (name "/Vs") (class "Default")
      (node (ref "JP1") (pin "18") (pinfunction "18_18") (pintype "passive"))
    )
    (net (code "119") (name "/XTAL1") (class "Default")
      (node (ref "C21") (pin "2") (pinfunction "2_2") (pintype "passive"))
      (node (ref "U1") (pin "22") (pinfunction "XTAL1_22") (pintype "passive"))
      (node (ref "Y1") (pin "1") (pinfunction "OSC1_1") (pintype "passive"))
    )
    (net (code "120") (name "/XTAL2") (class "Default")
      (node (ref "C31") (pin "2") (pinfunction "2_2") (pintype "passive"))
      (node (ref "U1") (pin "23") (pinfunction "XTAL2_23") (pintype "passive"))
      (node (ref "Y1") (pin "2") (pinfunction "OSC2_2") (pintype "passive"))
    )
    (net (code "121") (name "/res_but") (class "Default")
      (node (ref "D2") (pin "2") (pinfunction "K_2") (pintype "passive"))
      (node (ref "JP2") (pin "3") (pinfunction "3_3") (pintype "passive"))
      (node (ref "JP8") (pin "3") (pinfunction "3_3") (pintype "passive"))
    )
    (net (code "122") (name "GND") (class "Default")
      (node (ref "C15") (pin "1") (pinfunction "1_1") (pintype "passive"))
      (node (ref "C16") (pin "1") (pinfunction "1_1") (pintype "passive"))
      (node (ref "C17") (pin "1") (pinfunction "1_1") (pintype "passive"))
      (node (ref "C19") (pin "2") (pinfunction "2_2") (pintype "passive"))
      (node (ref "C21") (pin "1") (pinfunction "1_1") (pintype "passive"))
      (node (ref "C22") (pin "1") (pinfunction "1_1") (pintype "passive"))
      (node (ref "C23") (pin "2") (pinfunction "2_2") (pintype "passive"))
      (node (ref "C24") (pin "1") (pinfunction "1_1") (pintype "passive"))
      (node (ref "C25") (pin "1") (pinfunction "1_1") (pintype "passive"))
      (node (ref "C31") (pin "1") (pinfunction "1_1") (pintype "passive"))
      (node (ref "C33") (pin "1") (pinfunction "1_1") (pintype "passive"))
      (node (ref "C34") (pin "2") (pinfunction "2_2") (pintype "passive"))
      (node (ref "C35") (pin "2") (pinfunction "2_2") (pintype "passive"))
      (node (ref "C37") (pin "1") (pinfunction "1_1") (pintype "passive"))
      (node (ref "C38") (pin "1") (pinfunction "1_1") (pintype "passive"))
      (node (ref "C39") (pin "1") (pinfunction "1_1") (pintype "passive"))
      (node (ref "C40") (pin "1") (pinfunction "1_1") (pintype "passive"))
      (node (ref "C41") (pin "1") (pinfunction "1_1") (pintype "passive"))
      (node (ref "JP1") (pin "11") (pinfunction "11_11") (pintype "passive"))
      (node (ref "JP1") (pin "12") (pinfunction "12_12") (pintype "passive"))
      (node (ref "JP1") (pin "13") (pinfunction "13_13") (pintype "passive"))
      (node (ref "JP1") (pin "14") (pinfunction "14_14") (pintype "passive"))
      (node (ref "JP1") (pin "59") (pinfunction "59_59") (pintype "passive"))
      (node (ref "JP1") (pin "60") (pinfunction "60_60") (pintype "passive"))
      (node (ref "JP1") (pin "61") (pinfunction "61_61") (pintype "passive"))
      (node (ref "JP1") (pin "62") (pinfunction "62_62") (pintype "passive"))
      (node (ref "JP2") (pin "1") (pinfunction "1_1") (pintype "passive"))
      (node (ref "JP2") (pin "2") (pinfunction "2_2") (pintype "passive"))
      (node (ref "Q1") (pin "2") (pinfunction "E_2") (pintype "passive"))
      (node (ref "Q6") (pin "2") (pinfunction "E_2") (pintype "passive"))
      (node (ref "R29") (pin "1") (pinfunction "1_1") (pintype "passive"))
      (node (ref "R36") (pin "1") (pinfunction "1_1") (pintype "passive"))
      (node (ref "R57") (pin "1") (pinfunction "1_1") (pintype "passive"))
      (node (ref "R58") (pin "1") (pinfunction "1_1") (pintype "passive"))
      (node (ref "R60") (pin "1") (pinfunction "1_1") (pintype "passive"))
      (node (ref "U1") (pin "11") (pinfunction "Vssa_11") (pintype "passive"))
      (node (ref "U1") (pin "15") (pinfunction "Vss_15") (pintype "passive"))
      (node (ref "U1") (pin "31") (pinfunction "Vss_31") (pintype "passive"))
      (node (ref "U1") (pin "41") (pinfunction "Vss_41") (pintype "passive"))
      (node (ref "U1") (pin "55") (pinfunction "Vss_55") (pintype "passive"))
      (node (ref "U1") (pin "72") (pinfunction "Vss_72") (pintype "passive"))
      (node (ref "U1") (pin "83") (pinfunction "Vss_83") (pintype "passive"))
      (node (ref "U1") (pin "97") (pinfunction "Vss_97") (pintype "passive"))
      (node (ref "U12") (pin "2") (pinfunction "GND_2") (pintype "passive"))
      (node (ref "U12") (pin "8") (pinfunction "S_8") (pintype "passive"))
      (node (ref "U13") (pin "2") (pinfunction "GND_2") (pintype "power_in"))
      (node (ref "U19") (pin "2") (pinfunction "GND_2") (pintype "power_in"))
      (node (ref "U7") (pin "3") (pinfunction "GND_3") (pintype "passive"))
    )
    (net (code "123") (name "Net-(A1-Pad2)") (class "Default")
      (node (ref "A1") (pin "2") (pinfunction "2_2") (pintype "passive"))
      (node (ref "C19") (pin "1") (pinfunction "1_1") (pintype "passive"))
      (node (ref "R56") (pin "1") (pinfunction "1_1") (pintype "passive"))
      (node (ref "R57") (pin "2") (pinfunction "2_2") (pintype "passive"))
    )
    (net (code "124") (name "Net-(C22-Pad2)") (class "Default")
      (node (ref "C22") (pin "2") (pinfunction "2_2") (pintype "passive"))
      (node (ref "K1") (pin "3") (pinfunction "3_3") (pintype "passive"))
      (node (ref "R61") (pin "1") (pinfunction "1_1") (pintype "passive"))
      (node (ref "R64") (pin "1") (pinfunction "1_1") (pintype "passive"))
    )
    (net (code "125") (name "Net-(C23-Pad1)") (class "Default")
      (node (ref "C23") (pin "1") (pinfunction "1_1") (pintype "passive"))
      (node (ref "K1") (pin "1") (pinfunction "1_1") (pintype "passive"))
      (node (ref "R63") (pin "1") (pinfunction "1_1") (pintype "passive"))
      (node (ref "R65") (pin "1") (pinfunction "1_1") (pintype "passive"))
    )
    (net (code "126") (name "Net-(JP4-Pad15)") (class "Default")
      (node (ref "JP4") (pin "15") (pinfunction "15_15") (pintype "passive"))
      (node (ref "R29") (pin "2") (pinfunction "2_2") (pintype "passive"))
    )
    (net (code "127") (name "Net-(Q1-B)") (class "Default")
      (node (ref "Q1") (pin "1") (pinfunction "B_1") (pintype "passive"))
      (node (ref "R34") (pin "2") (pinfunction "2_2") (pintype "passive"))
      (node (ref "R36") (pin "2") (pinfunction "2_2") (pintype "passive"))
    )
    (net (code "128") (name "Net-(Q1-C)") (class "Default")
      (node (ref "A1") (pin "1") (pinfunction "1_1") (pintype "passive"))
      (node (ref "Q1") (pin "3") (pinfunction "C_3") (pintype "passive"))
    )
    (net (code "129") (name "Net-(Q5-G)") (class "Default")
      (node (ref "JP8") (pin "1") (pinfunction "1_1") (pintype "passive"))
      (node (ref "JP8") (pin "2") (pinfunction "2_2") (pintype "passive"))
      (node (ref "Q5") (pin "1") (pinfunction "G_1") (pintype "passive"))
      (node (ref "U13") (pin "1") (pinfunction "~{RST}_1") (pintype "power_in"))
    )
    (net (code "130") (name "Net-(Q5-S)") (class "Default")
      (node (ref "Q5") (pin "2") (pinfunction "S_2") (pintype "passive"))
      (node (ref "U13") (pin "4") (pinfunction "WDI_4") (pintype "passive"))
    )
    (net (code "131") (name "Net-(Q6-B)") (class "Default")
      (node (ref "Q6") (pin "1") (pinfunction "B_1") (pintype "passive"))
      (node (ref "R35") (pin "2") (pinfunction "2_2") (pintype "passive"))
      (node (ref "R58") (pin "2") (pinfunction "2_2") (pintype "passive"))
    )
    (net (code "132") (name "Net-(Q6-C)") (class "Default")
      (node (ref "K1") (pin "5") (pinfunction "5_5") (pintype "passive"))
      (node (ref "Q6") (pin "3") (pinfunction "C_3") (pintype "passive"))
    )
    (net (code "133") (name "Net-(U7-outA)") (class "Default")
      (node (ref "R40") (pin "2") (pinfunction "2_2") (pintype "passive"))
      (node (ref "U7") (pin "7") (pinfunction "outA_7") (pintype "passive"))
    )
    (net (code "134") (name "Net-(U7-outB)") (class "Default")
      (node (ref "R41") (pin "2") (pinfunction "2_2") (pintype "passive"))
      (node (ref "U7") (pin "5") (pinfunction "outB_5") (pintype "passive"))
    )
    (net (code "135") (name "Net-(U9-IN+)") (class "Default")
      (node (ref "C35") (pin "1") (pinfunction "1_1") (pintype "passive"))
      (node (ref "R60") (pin "2") (pinfunction "2_2") (pintype "passive"))
      (node (ref "R65") (pin "2") (pinfunction "2_2") (pintype "passive"))
      (node (ref "U9") (pin "3") (pinfunction "IN+_3") (pintype "input"))
    )
    (net (code "136") (name "Net-(U9-IN-)") (class "Default")
      (node (ref "C32") (pin "1") (pinfunction "1_1") (pintype "passive"))
      (node (ref "R59") (pin "2") (pinfunction "2_2") (pintype "passive"))
      (node (ref "R64") (pin "2") (pinfunction "2_2") (pintype "passive"))
      (node (ref "U9") (pin "2") (pinfunction "IN-_2") (pintype "input"))
    )
    (net (code "137") (name "Net-(U9-OUT)") (class "Default")
      (node (ref "C24") (pin "2") (pinfunction "2_2") (pintype "passive"))
      (node (ref "C32") (pin "2") (pinfunction "2_2") (pintype "passive"))
      (node (ref "R59") (pin "1") (pinfunction "1_1") (pintype "passive"))
      (node (ref "R66") (pin "1") (pinfunction "1_1") (pintype "passive"))
      (node (ref "U9") (pin "6") (pinfunction "OUT_6") (pintype "output"))
    )
    (net (code "138") (name "unconnected-(JP1-Pad3)") (class "Default")
      (node (ref "JP1") (pin "3") (pinfunction "3_3") (pintype "passive"))
    )
    (net (code "139") (name "unconnected-(JP1-Pad4)") (class "Default")
      (node (ref "JP1") (pin "4") (pinfunction "4_4") (pintype "passive"))
    )
    (net (code "140") (name "unconnected-(JP1-Pad15)") (class "Default")
      (node (ref "JP1") (pin "15") (pinfunction "15_15") (pintype "passive"))
    )
    (net (code "141") (name "unconnected-(JP1-Pad16)") (class "Default")
      (node (ref "JP1") (pin "16") (pinfunction "16_16") (pintype "passive"))
    )
    (net (code "142") (name "unconnected-(JP1-Pad29)") (class "Default")
      (node (ref "JP1") (pin "29") (pinfunction "29_29") (pintype "passive"))
    )
    (net (code "143") (name "unconnected-(JP1-Pad30)") (class "Default")
      (node (ref "JP1") (pin "30") (pinfunction "30_30") (pintype "passive"))
    )
    (net (code "144") (name "unconnected-(JP1-Pad31)") (class "Default")
      (node (ref "JP1") (pin "31") (pinfunction "31_31") (pintype "passive"))
    )
    (net (code "145") (name "unconnected-(JP1-Pad32)") (class "Default")
      (node (ref "JP1") (pin "32") (pinfunction "32_32") (pintype "passive"))
    )
    (net (code "146") (name "unconnected-(JP1-Pad42)") (class "Default")
      (node (ref "JP1") (pin "42") (pinfunction "42_42") (pintype "passive"))
    )
    (net (code "147") (name "unconnected-(K1-Pad2)") (class "Default")
      (node (ref "K1") (pin "2") (pinfunction "2_2") (pintype "passive"))
    )
    (net (code "148") (name "unconnected-(U1-RTCK-Pad100)") (class "Default")
      (node (ref "U1") (pin "100") (pinfunction "RTCK_100") (pintype "passive"))
    )
    (net (code "149") (name "unconnected-(U1-TCK-Pad5)") (class "Default")
      (node (ref "U1") (pin "5") (pinfunction "TCK_5") (pintype "passive"))
    )
    (net (code "150") (name "unconnected-(U1-TDI-Pad2)") (class "Default")
      (node (ref "U1") (pin "2") (pinfunction "TDI_2") (pintype "passive"))
    )
    (net (code "151") (name "unconnected-(U1-TDO-Pad1)") (class "Default")
      (node (ref "U1") (pin "1") (pinfunction "TDO_1") (pintype "passive"))
    )
    (net (code "152") (name "unconnected-(U1-TMS-Pad3)") (class "Default")
      (node (ref "U1") (pin "3") (pinfunction "TMS_3") (pintype "passive"))
    )
    (net (code "153") (name "unconnected-(U1-~{RSTOUT}-Pad14)") (class "Default")
      (node (ref "U1") (pin "14") (pinfunction "~{RSTOUT}_14") (pintype "passive"))
    )
    (net (code "154") (name "unconnected-(U1-~{TRST}-Pad4)") (class "Default")
      (node (ref "U1") (pin "4") (pinfunction "~{TRST}_4") (pintype "passive"))
    )
    (net (code "155") (name "unconnected-(U9-NC-Pad5)") (class "Default")
      (node (ref "U9") (pin "5") (pinfunction "NC_5") (pintype "passive"))
    )
    (net (code "156") (name "unconnected-(U9-VOSTRIM-Pad1)") (class "Default")
      (node (ref "U9") (pin "1") (pinfunction "VOSTRIM_1") (pintype "passive"))
    )
    (net (code "157") (name "unconnected-(U9-VOSTRIM-Pad8)") (class "Default")
      (node (ref "U9") (pin "8") (pinfunction "VOSTRIM_8") (pintype "passive"))
    )
    (net (code "158") (name "unconnected-(U12-Vref-Pad5)") (class "Default")
      (node (ref "U12") (pin "5") (pinfunction "Vref_5") (pintype "passive"))
    )
    (net (code "159") (name "unconnected-(U13-~{MR}-Pad3)") (class "Default")
      (node (ref "U13") (pin "3") (pinfunction "~{MR}_3") (pintype "input"))
    )
    (net (code "160") (name "unconnected-(U19-NC-Pad4)") (class "Default")
      (node (ref "U19") (pin "4") (pinfunction "NC_4") (pintype "passive"))
    )
  )
)
